# power.net
KiCad netlist of a schematic drawn in Altium Designer
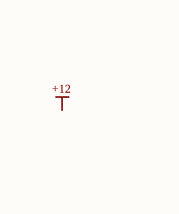
[diagram p0: power.SchDoc, left]
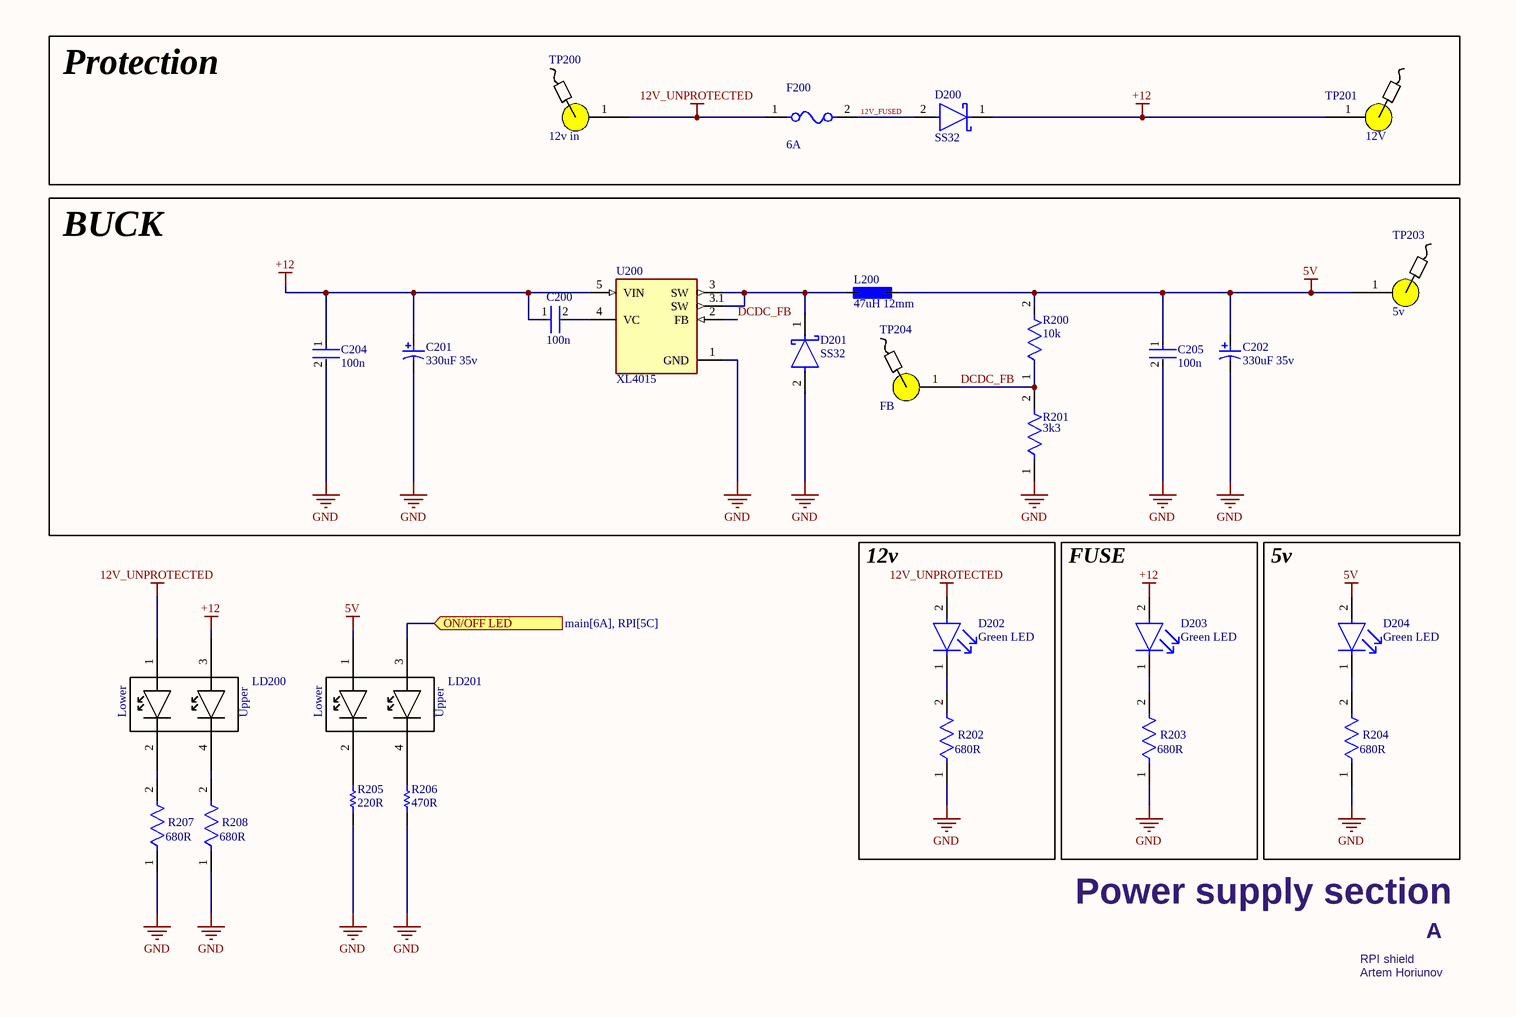
[diagram p1: power.SchDoc, right]

(export (version "E")
  (design (tool "Eeschema 10.0.6"))
  (components
    (comp (ref "C200")
      (value "100n")
      (footprint "FP-C0603C-CF-MFG")
      (description "CAP CER 0.1UF 50V X7R 0603")
      (fields (field (name "TOLERANCE") "0.1") (field (name "MANUFACTURER") "KEMET"))
      (libsource (lib "Altium Content Vault") (part "b4654b650e69147ec39a6b967a45e02"))
    )
    (comp (ref "C201")
      (value "330uF 35v")
      (footprint "PNSC-EEE-FK1V331P_L")
      (description "Aluminum Electrolytic Capacitor, 330 uF, 35 V, -55 to 105 degC, 2-Pin CAPAE, RoHS, Tape and Reel")
      (fields (field (name "MANUFACTURER") "Panasonic"))
      (libsource (lib "Altium Content Vault") (part "CAP-P-2"))
    )
    (comp (ref "C202")
      (value "330uF 35v")
      (footprint "PNSC-EEE-FK1V331P_L")
      (description "Aluminum Electrolytic Capacitor, 330 uF, 35 V, -55 to 105 degC, 2-Pin CAPAE, RoHS, Tape and Reel")
      (fields (field (name "MANUFACTURER") "Panasonic"))
      (libsource (lib "Altium Content Vault") (part "CAP-P-2"))
    )
    (comp (ref "C204")
      (value "100n")
      (footprint "FP-C0603C-CF-MFG")
      (description "CAP CER 0.1UF 50V X7R 0603")
      (fields (field (name "TOLERANCE") "0.1") (field (name "MANUFACTURER") "KEMET"))
      (libsource (lib "Altium Content Vault") (part "b4654b650e69147ec39a6b967a45e02"))
    )
    (comp (ref "C205")
      (value "100n")
      (footprint "FP-C0603C-CF-MFG")
      (description "CAP CER 0.1UF 50V X7R 0603")
      (fields (field (name "TOLERANCE") "0.1") (field (name "MANUFACTURER") "KEMET"))
      (libsource (lib "Altium Content Vault") (part "b4654b650e69147ec39a6b967a45e02"))
    )
    (comp (ref "D200")
      (value "SS32")
      (footprint "FP-403AG-MFG")
      (description "SS32 Rectifier Diode, Schottky, 1 Phase, 1 Element, 3A, 20V V(RRM), Silicon, DO-214AB")
      (libsource (lib "Altium Content Vault") (part "c1678fac7984e62e0809fbf79c06691"))
    )
    (comp (ref "D201")
      (value "SS32")
      (footprint "FP-403AG-MFG")
      (description "SS32 Rectifier Diode, Schottky, 1 Phase, 1 Element, 3A, 20V V(RRM), Silicon, DO-214AB")
      (libsource (lib "Altium Content Vault") (part "c1678fac7984e62e0809fbf79c06691"))
    )
    (comp (ref "D202")
      (value "Green LED")
      (footprint "FP-HSME-C191-MFG")
      (description "LED GREEN DIFFUSED 0603 SMD")
      (fields (field (name "MANUFACTURER") "Broadcom") (field (name "MANUFACTURER PART NUMBER") "HSME-C191"))
      (libsource (lib "Altium Content Vault") (part "8706943c75ba83719d021d2fdc84c58"))
    )
    (comp (ref "D203")
      (value "Green LED")
      (footprint "FP-HSME-C191-MFG")
      (description "LED GREEN DIFFUSED 0603 SMD")
      (fields (field (name "MANUFACTURER") "Broadcom") (field (name "MANUFACTURER PART NUMBER") "HSME-C191"))
      (libsource (lib "Altium Content Vault") (part "8706943c75ba83719d021d2fdc84c58"))
    )
    (comp (ref "D204")
      (value "Green LED")
      (footprint "FP-HSME-C191-MFG")
      (description "LED GREEN DIFFUSED 0603 SMD")
      (fields (field (name "MANUFACTURER") "Broadcom") (field (name "MANUFACTURER PART NUMBER") "HSME-C191"))
      (libsource (lib "Altium Content Vault") (part "8706943c75ba83719d021d2fdc84c58"))
    )
    (comp (ref "F200")
      (value "6A")
      (footprint "FP-0466-MFG")
      (libsource (lib "Altium Content Vault") (part "5bcf9b9f640e542cf0359d10258e979"))
    )
    (comp (ref "L200")
      (value "47uH 12mm")
      (footprint "DE1207")
      (description "Inductor: wire; 22uH; 4.7A; 0.036Î©; SMD; 12x12x8mm; Â±20")
      (fields (field (name "MF") "FerroCore") (field (name "MP") "DE1207-22"))
      (libsource (lib "DE1207-22") (part "DE1207-22"))
    )
    (comp (ref "LD200")
      (value "~")
      (footprint "LedHolder:LED_HOLDER")
      (libsource (lib "LedHolder") (part "DoubleStack_Side_Led_3mm"))
    )
    (comp (ref "LD201")
      (value "~")
      (footprint "LedHolder:LED_HOLDER")
      (libsource (lib "LedHolder") (part "DoubleStack_Side_Led_3mm"))
    )
    (comp (ref "R200")
      (value "10k")
      (footprint "FP-RC0603-0_55-IPC_C")
      (description "RES 10K OHM 1% 1/10W 0603")
      (fields (field (name "TOLERANCE") "1%"))
      (libsource (lib "Altium Content Vault") (part "1029c3af85768c4190bb7ad29bc67b5"))
    )
    (comp (ref "R201")
      (value "3k3")
      (footprint "FP-RC0603-0_55-MFG")
      (fields (field (name "TOLERANCE") "1%"))
      (libsource (lib "Altium Content Vault") (part "1029c3af85768c4190bb7ad29bc67b5"))
    )
    (comp (ref "R202")
      (value "680R")
      (footprint "FP-CRCW0603-e3-MFG")
      (description "RES Thick Film, 680Ω, 1%, 0.1W, 100ppm/°C, 0603")
      (fields (field (name "TOLERANCE") "1%"))
      (libsource (lib "Altium Content Vault") (part "1029c3af85768c4190bb7ad29bc67b5"))
    )
    (comp (ref "R203")
      (value "680R")
      (footprint "FP-CRCW0603-e3-MFG")
      (description "RES Thick Film, 680Ω, 1%, 0.1W, 100ppm/°C, 0603")
      (fields (field (name "TOLERANCE") "1%"))
      (libsource (lib "Altium Content Vault") (part "1029c3af85768c4190bb7ad29bc67b5"))
    )
    (comp (ref "R204")
      (value "680R")
      (footprint "FP-CRCW0603-e3-MFG")
      (description "RES Thick Film, 680Ω, 1%, 0.1W, 100ppm/°C, 0603")
      (fields (field (name "TOLERANCE") "1%"))
      (libsource (lib "Altium Content Vault") (part "1029c3af85768c4190bb7ad29bc67b5"))
    )
    (comp (ref "R205")
      (value "220R")
      (footprint "RESC1608X55X25ML10T15")
      (libsource (lib "Altium Content Vault") (part "RES-2"))
    )
    (comp (ref "R206")
      (value "470R")
      (footprint "RESC1608X55X25LL10T15")
      (libsource (lib "Altium Content Vault") (part "RES-2"))
    )
    (comp (ref "R207")
      (value "680R")
      (footprint "FP-CRCW0603-e3-MFG")
      (description "RES Thick Film, 680Ω, 1%, 0.1W, 100ppm/°C, 0603")
      (fields (field (name "TOLERANCE") "1%"))
      (libsource (lib "Altium Content Vault") (part "1029c3af85768c4190bb7ad29bc67b5"))
    )
    (comp (ref "R208")
      (value "680R")
      (footprint "FP-CRCW0603-e3-MFG")
      (description "RES Thick Film, 680Ω, 1%, 0.1W, 100ppm/°C, 0603")
      (fields (field (name "TOLERANCE") "1%"))
      (libsource (lib "Altium Content Vault") (part "1029c3af85768c4190bb7ad29bc67b5"))
    )
    (comp (ref "TP200")
      (value "12v in")
      (footprint "TestPoint")
      (libsource (lib "TestPoint") (part "TestPoint"))
    )
    (comp (ref "TP201")
      (value "12V")
      (footprint "TestPoint")
      (libsource (lib "TestPoint") (part "TestPoint"))
    )
    (comp (ref "TP203") (value "5v") (footprint "TestPoint") (libsource (lib "TestPoint") (part "TestPoint")))
    (comp (ref "TP204") (value "FB") (footprint "TestPoint") (libsource (lib "TestPoint") (part "TestPoint")))
    (comp (ref "U200")
      (value "XL4015")
      (footprint "CONV_XL4015")
      (description "5A 180KHz 36V Buck DC to DC Converter")
      (libsource (lib "XL4015(2)") (part "XL4015"))
    )
  )
  (nets
    (net (code "1") (name "+12") (class "Default")
      (node (ref "C200") (pin "1") (pinfunction "1_1") (pintype "passive"))
      (node (ref "C201") (pin "1") (pinfunction "1_1") (pintype "passive"))
      (node (ref "C204") (pin "1") (pinfunction "1_1") (pintype "passive"))
      (node (ref "D200") (pin "1") (pinfunction "C_1") (pintype "passive"))
      (node (ref "D203") (pin "2") (pinfunction "A_2") (pintype "passive"))
      (node (ref "LD200") (pin "3") (pintype "passive"))
      (node (ref "TP201") (pin "1") (pintype "passive"))
      (node (ref "U200") (pin "5") (pinfunction "VIN_5") (pintype "input"))
    )
    (net (code "2") (name "/12V_FUSED") (class "Default")
      (node (ref "D200") (pin "2") (pinfunction "A_2") (pintype "passive"))
      (node (ref "F200") (pin "2") (pinfunction "2_2") (pintype "passive"))
    )
    (net (code "3") (name "/DCDC_FB") (class "Default")
      (node (ref "R200") (pin "1") (pinfunction "1_1") (pintype "passive"))
      (node (ref "R201") (pin "2") (pinfunction "2_2") (pintype "passive"))
      (node (ref "TP204") (pin "1") (pintype "passive"))
      (node (ref "U200") (pin "2") (pinfunction "FB_2") (pintype "input"))
    )
    (net (code "4") (name "/ON{slash}OFF LED") (class "Default")
      (node (ref "LD201") (pin "3") (pintype "passive"))
    )
    (net (code "5") (name "5V") (class "Default")
      (node (ref "C202") (pin "1") (pinfunction "1_1") (pintype "passive"))
      (node (ref "C205") (pin "1") (pinfunction "1_1") (pintype "passive"))
      (node (ref "D204") (pin "2") (pinfunction "A_2") (pintype "passive"))
      (node (ref "L200") (pin "2") (pinfunction "2_2") (pintype "passive"))
      (node (ref "LD201") (pin "1") (pintype "passive"))
      (node (ref "R200") (pin "2") (pinfunction "2_2") (pintype "passive"))
      (node (ref "TP203") (pin "1") (pintype "passive"))
    )
    (net (code "6") (name "12V_UNPROTECTED") (class "Default")
      (node (ref "D202") (pin "2") (pinfunction "A_2") (pintype "passive"))
      (node (ref "F200") (pin "1") (pinfunction "1_1") (pintype "passive"))
      (node (ref "LD200") (pin "1") (pintype "passive"))
      (node (ref "TP200") (pin "1") (pintype "passive"))
    )
    (net (code "7") (name "GND") (class "Default")
      (node (ref "C201") (pin "2") (pinfunction "2_2") (pintype "passive"))
      (node (ref "C202") (pin "2") (pinfunction "2_2") (pintype "passive"))
      (node (ref "C204") (pin "2") (pinfunction "2_2") (pintype "passive"))
      (node (ref "C205") (pin "2") (pinfunction "2_2") (pintype "passive"))
      (node (ref "D201") (pin "2") (pinfunction "A_2") (pintype "passive"))
      (node (ref "R201") (pin "1") (pinfunction "1_1") (pintype "passive"))
      (node (ref "R202") (pin "1") (pinfunction "1_1") (pintype "passive"))
      (node (ref "R203") (pin "1") (pinfunction "1_1") (pintype "passive"))
      (node (ref "R204") (pin "1") (pinfunction "1_1") (pintype "passive"))
      (node (ref "R205") (pin "1") (pinfunction "1_1") (pintype "passive"))
      (node (ref "R206") (pin "1") (pinfunction "1_1") (pintype "passive"))
      (node (ref "R207") (pin "1") (pinfunction "1_1") (pintype "passive"))
      (node (ref "R208") (pin "1") (pinfunction "1_1") (pintype "passive"))
      (node (ref "U200") (pin "1") (pinfunction "GND_1") (pintype "power_in"))
    )
    (net (code "8") (name "Net-(D201-C)") (class "Default")
      (node (ref "D201") (pin "1") (pinfunction "C_1") (pintype "passive"))
      (node (ref "L200") (pin "1") (pinfunction "1_1") (pintype "passive"))
      (node (ref "U200") (pin "3") (pinfunction "SW_3") (pintype "output"))
      (node (ref "U200") (pin "3.1") (pinfunction "SW_3.1") (pintype "output"))
    )
    (net (code "9") (name "Net-(D202-C)") (class "Default")
      (node (ref "D202") (pin "1") (pinfunction "C_1") (pintype "passive"))
      (node (ref "R202") (pin "2") (pinfunction "2_2") (pintype "passive"))
    )
    (net (code "10") (name "Net-(D203-C)") (class "Default")
      (node (ref "D203") (pin "1") (pinfunction "C_1") (pintype "passive"))
      (node (ref "R203") (pin "2") (pinfunction "2_2") (pintype "passive"))
    )
    (net (code "11") (name "Net-(D204-C)") (class "Default")
      (node (ref "D204") (pin "1") (pinfunction "C_1") (pintype "passive"))
      (node (ref "R204") (pin "2") (pinfunction "2_2") (pintype "passive"))
    )
    (net (code "12") (name "Net-(LD200-Pad2)") (class "Default")
      (node (ref "LD200") (pin "2") (pintype "passive"))
      (node (ref "R207") (pin "2") (pinfunction "2_2") (pintype "passive"))
    )
    (net (code "13") (name "Net-(LD200-Pad4)") (class "Default")
      (node (ref "LD200") (pin "4") (pintype "passive"))
      (node (ref "R208") (pin "2") (pinfunction "2_2") (pintype "passive"))
    )
    (net (code "14") (name "Net-(LD201-Pad2)") (class "Default")
      (node (ref "LD201") (pin "2") (pintype "passive"))
      (node (ref "R205") (pin "2") (pinfunction "2_2") (pintype "passive"))
    )
    (net (code "15") (name "Net-(LD201-Pad4)") (class "Default")
      (node (ref "LD201") (pin "4") (pintype "passive"))
      (node (ref "R206") (pin "2") (pinfunction "2_2") (pintype "passive"))
    )
    (net (code "16") (name "Net-(U200-VC)") (class "Default")
      (node (ref "C200") (pin "2") (pinfunction "2_2") (pintype "passive"))
      (node (ref "U200") (pin "4") (pinfunction "VC_4") (pintype "passive"))
    )
  )
)
